# SCH_3S_10A_BMS_2022-07-15.net
KiCad netlist of a schematic drawn in EasyEDA
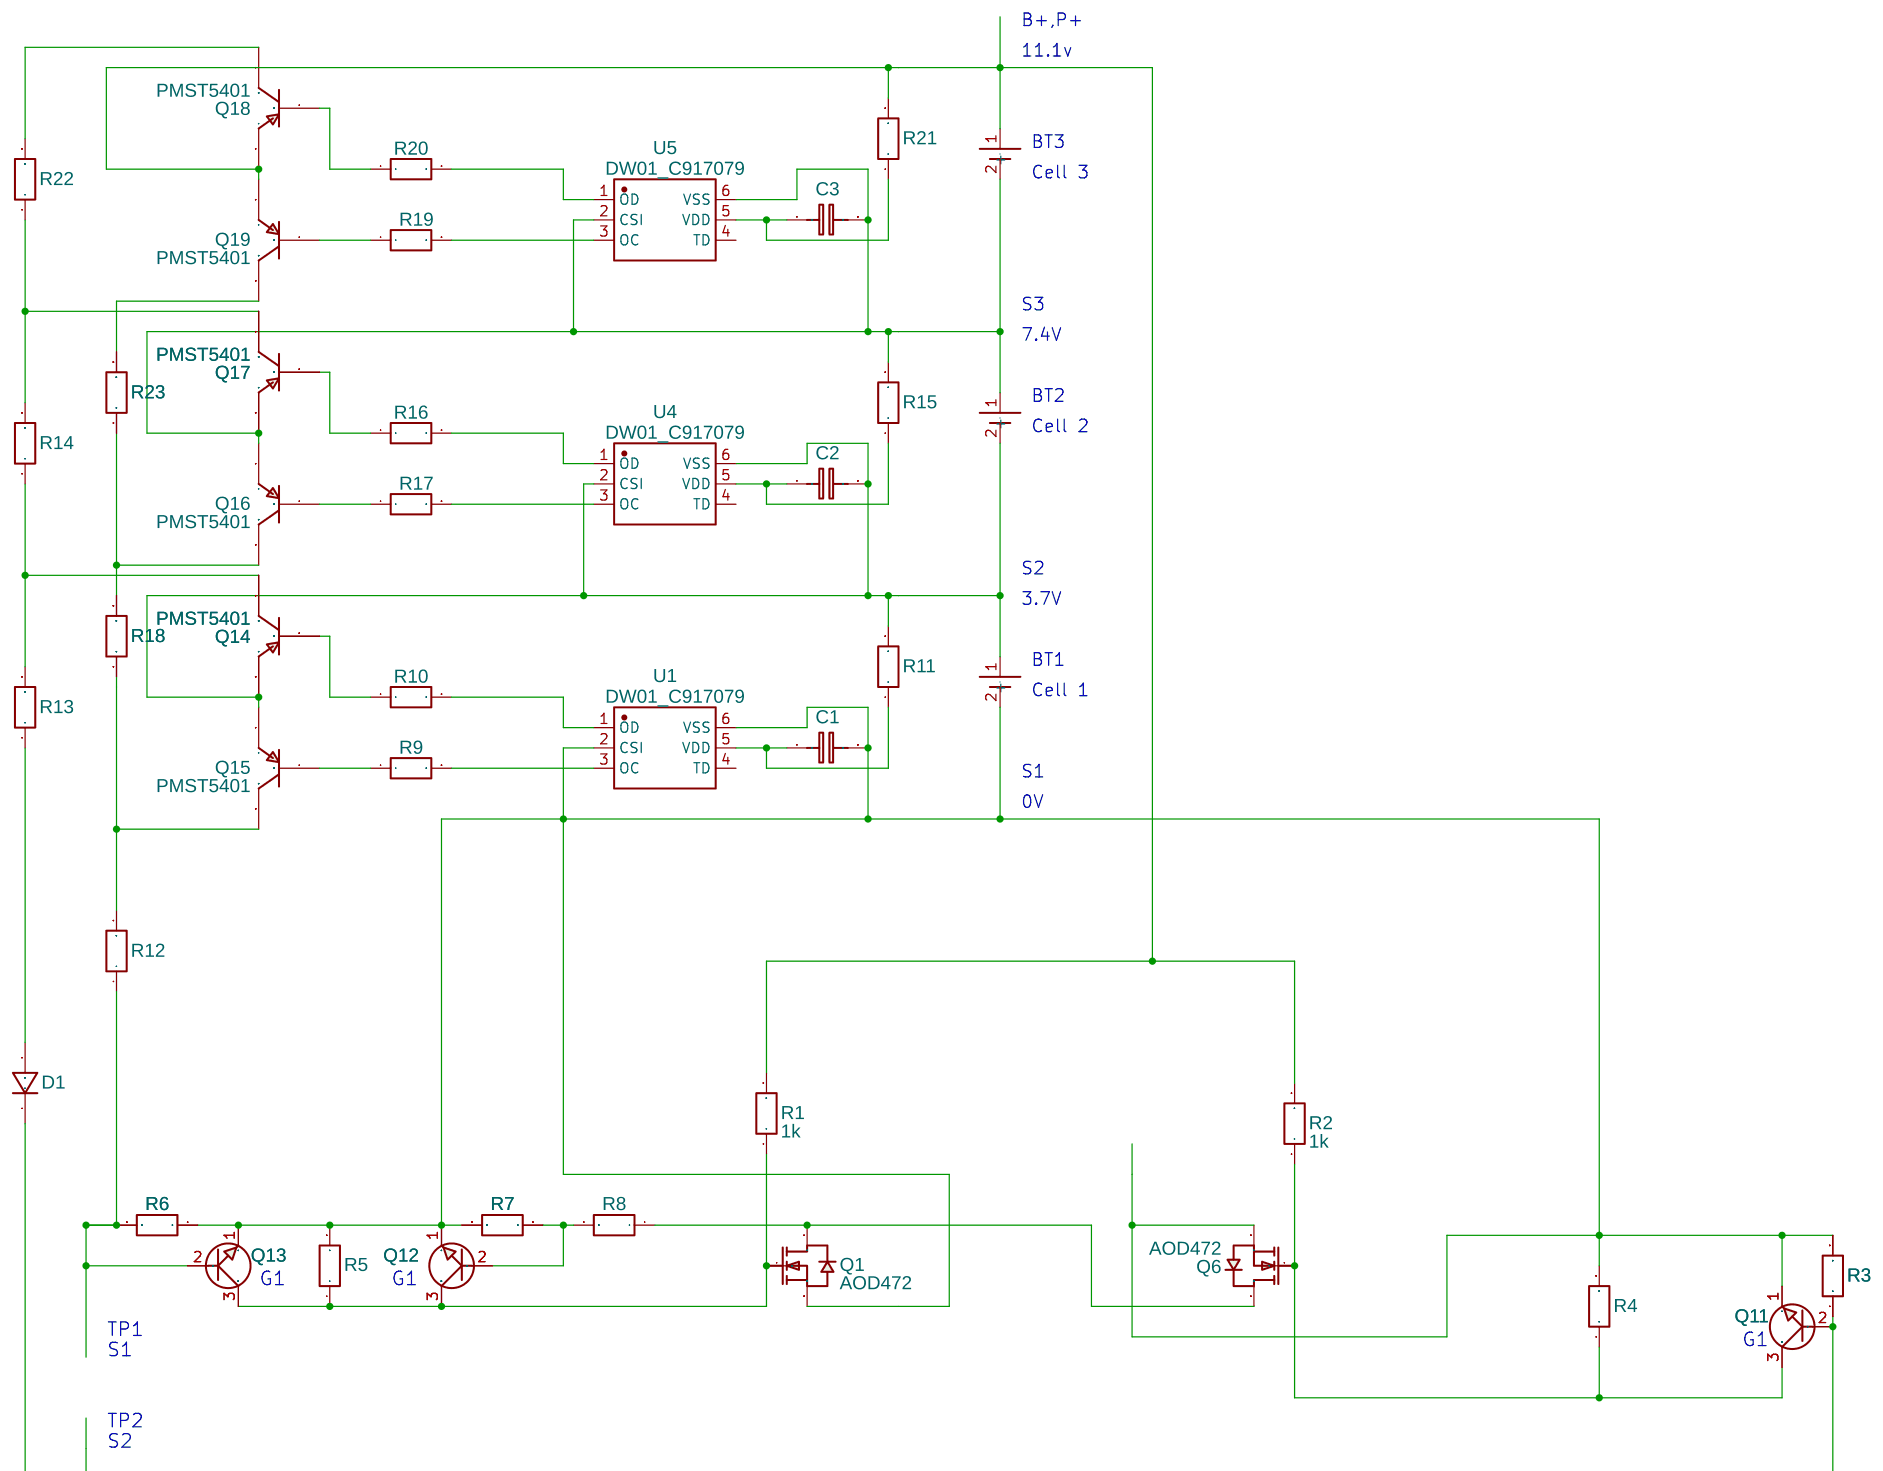
[diagram p0: 3s 10A Schematic]
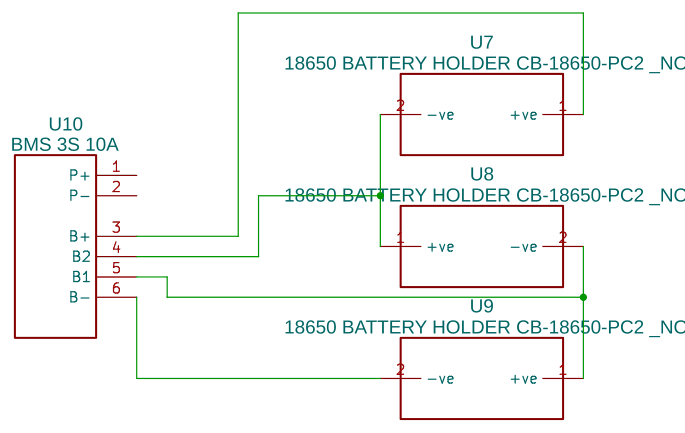
[diagram p1: 12v connection]

(export (version "E")
  (design (tool "Eeschema 10.0.6"))
  (components
    (comp (ref "C1") (value "0.1u") (libsource (lib "") (part "C_0603_EU")))
    (comp (ref "C2") (value "0.1u") (libsource (lib "") (part "C_0603_EU")))
    (comp (ref "C3") (value "0.1u") (libsource (lib "") (part "C_0603_EU")))
    (comp (ref "D1")
      (value "1N4007W")
      (fields (field (name "BOM_Supplier Part") "C328592"))
      (libsource (lib "") (part "1N4007W"))
    )
    (comp (ref "Q1")
      (value "AOD472")
      (fields (field (name "BOM_Supplier Part") "C693172"))
      (libsource (lib "") (part "AOD472"))
    )
    (comp (ref "Q6")
      (value "AOD472")
      (fields (field (name "BOM_Supplier Part") "C693172"))
      (libsource (lib "") (part "AOD472_1"))
    )
    (comp (ref "Q11") (value "2N2222") (libsource (lib "") (part "2N2222")))
    (comp (ref "Q12") (value "2N2222") (libsource (lib "") (part "2N2222")))
    (comp (ref "Q13") (value "2N2222") (libsource (lib "") (part "2N2222_1")))
    (comp (ref "Q14") (value "PMST5401") (libsource (lib "") (part "PMST5401_1")))
    (comp (ref "Q15") (value "PMST5401") (libsource (lib "") (part "PMST5401")))
    (comp (ref "Q16") (value "PMST5401") (libsource (lib "") (part "PMST5401")))
    (comp (ref "Q17") (value "PMST5401") (libsource (lib "") (part "PMST5401_1")))
    (comp (ref "Q18") (value "PMST5401") (libsource (lib "") (part "PMST5401_1")))
    (comp (ref "Q19") (value "PMST5401") (libsource (lib "") (part "PMST5401")))
    (comp (ref "R1") (value "1k") (libsource (lib "") (part "R_0603_EU_1")))
    (comp (ref "R2") (value "1k") (libsource (lib "") (part "R_0603_EU_1")))
    (comp (ref "R3") (value "1k") (libsource (lib "") (part "R_0603_EU_1")))
    (comp (ref "R4") (value "1k") (libsource (lib "") (part "R_0603_EU_1")))
    (comp (ref "R5") (value "1k") (libsource (lib "") (part "R_0603_EU_1")))
    (comp (ref "R6") (value "1k") (libsource (lib "") (part "R_0603_EU")))
    (comp (ref "R7") (value "1k") (libsource (lib "") (part "R_0603_EU")))
    (comp (ref "R8") (value "1k") (libsource (lib "") (part "R_0603_EU")))
    (comp (ref "R9") (value "1k") (libsource (lib "") (part "R_0603_EU_2")))
    (comp (ref "R10") (value "1k") (libsource (lib "") (part "R_0603_EU_2")))
    (comp (ref "R11") (value "1k") (libsource (lib "") (part "R_0603_EU_1")))
    (comp (ref "R12") (value "1k") (libsource (lib "") (part "R_0603_EU_1")))
    (comp (ref "R13") (value "1k") (libsource (lib "") (part "R_0603_EU_1")))
    (comp (ref "R14") (value "1k") (libsource (lib "") (part "R_0603_EU_1")))
    (comp (ref "R15") (value "1k") (libsource (lib "") (part "R_0603_EU_1")))
    (comp (ref "R16") (value "1k") (libsource (lib "") (part "R_0603_EU_2")))
    (comp (ref "R17") (value "1k") (libsource (lib "") (part "R_0603_EU_2")))
    (comp (ref "R18") (value "1k") (libsource (lib "") (part "R_0603_EU_1")))
    (comp (ref "R19") (value "1k") (libsource (lib "") (part "R_0603_EU_2")))
    (comp (ref "R20") (value "1k") (libsource (lib "") (part "R_0603_EU_2")))
    (comp (ref "R21") (value "1k") (libsource (lib "") (part "R_0603_EU_1")))
    (comp (ref "R22") (value "1k") (libsource (lib "") (part "R_0603_EU_1")))
    (comp (ref "R23") (value "1k") (libsource (lib "") (part "R_0603_EU_1")))
    (comp (ref "U1")
      (value "DW01_C917079")
      (fields (field (name "BOM_Manufacturer Part") "DW01") (field (name "BOM_Supplier Part") "C917079"))
      (libsource (lib "") (part "DW01_C917079"))
    )
    (comp (ref "U2") (value "Li-ion battery") (libsource (lib "") (part "Li-ion battery")))
    (comp (ref "U3") (value "Li-ion battery") (libsource (lib "") (part "Li-ion battery")))
    (comp (ref "U4")
      (value "DW01_C917079")
      (fields (field (name "BOM_Manufacturer Part") "DW01") (field (name "BOM_Supplier Part") "C917079"))
      (libsource (lib "") (part "DW01_C917079"))
    )
    (comp (ref "U5")
      (value "DW01_C917079")
      (fields (field (name "BOM_Manufacturer Part") "DW01") (field (name "BOM_Supplier Part") "C917079"))
      (libsource (lib "") (part "DW01_C917079"))
    )
    (comp (ref "U6") (value "Li-ion battery") (libsource (lib "") (part "Li-ion battery")))
    (comp (ref "U7")
      (value "18650 BATTERY HOLDER CB-18650-PC2 _NOTEMP COPY")
      (libsource (lib "") (part "18650 BATTERY HOLDER CB-18650-PC2 _NOTEMP COPY_1"))
    )
    (comp (ref "U8")
      (value "18650 BATTERY HOLDER CB-18650-PC2 _NOTEMP COPY")
      (libsource (lib "") (part "18650 BATTERY HOLDER CB-18650-PC2 _NOTEMP COPY"))
    )
    (comp (ref "U9")
      (value "18650 BATTERY HOLDER CB-18650-PC2 _NOTEMP COPY")
      (libsource (lib "") (part "18650 BATTERY HOLDER CB-18650-PC2 _NOTEMP COPY_1"))
    )
    (comp (ref "U10") (value "BMS 3S 10A") (libsource (lib "") (part "BMS 3S 10A")))
  )
  (nets
    (net (code "1") (name "Net-(D1-Pad2)") (class "Default")
      (node (ref "D1") (pin "2") (pinfunction "2_2") (pintype "unspecified"))
      (node (ref "R13") (pin "1") (pinfunction "1_1") (pintype "unspecified"))
    )
    (net (code "2") (name "Net-(Q1-D)") (class "Default")
      (node (ref "Q1") (pin "2") (pinfunction "D_2") (pintype "unspecified"))
      (node (ref "Q6") (pin "2") (pinfunction "D_2") (pintype "unspecified"))
      (node (ref "R8") (pin "1") (pinfunction "1_1") (pintype "unspecified"))
    )
    (net (code "3") (name "Net-(Q1-G)") (class "Default")
      (node (ref "Q1") (pin "1") (pinfunction "G_1") (pintype "unspecified"))
      (node (ref "Q12") (pin "3") (pinfunction "C_3") (pintype "unspecified"))
      (node (ref "Q13") (pin "3") (pinfunction "C_3") (pintype "unspecified"))
      (node (ref "R1") (pin "1") (pinfunction "1_1") (pintype "unspecified"))
      (node (ref "R5") (pin "1") (pinfunction "1_1") (pintype "unspecified"))
    )
    (net (code "4") (name "Net-(Q1-S)") (class "Default")
      (node (ref "C1") (pin "2") (pinfunction "2_2") (pintype "unspecified"))
      (node (ref "Q1") (pin "3") (pinfunction "S_3") (pintype "unspecified"))
      (node (ref "Q11") (pin "1") (pinfunction "E_1") (pintype "unspecified"))
      (node (ref "Q12") (pin "1") (pinfunction "E_1") (pintype "unspecified"))
      (node (ref "Q13") (pin "1") (pinfunction "E_1") (pintype "unspecified"))
      (node (ref "Q6") (pin "3") (pinfunction "S_3") (pintype "unspecified"))
      (node (ref "R3") (pin "2") (pinfunction "2_2") (pintype "unspecified"))
      (node (ref "R4") (pin "2") (pinfunction "2_2") (pintype "unspecified"))
      (node (ref "R5") (pin "2") (pinfunction "2_2") (pintype "unspecified"))
      (node (ref "R6") (pin "1") (pinfunction "1_1") (pintype "unspecified"))
      (node (ref "R7") (pin "2") (pinfunction "2_2") (pintype "unspecified"))
      (node (ref "U1") (pin "2") (pinfunction "CSI_2") (pintype "unspecified"))
      (node (ref "U1") (pin "6") (pinfunction "VSS_6") (pintype "unspecified"))
      (node (ref "U2") (pin "2") (pinfunction "-_2") (pintype "unspecified"))
    )
    (net (code "5") (name "Net-(Q11-B)") (class "Default")
      (node (ref "D1") (pin "1") (pinfunction "1_1") (pintype "unspecified"))
      (node (ref "Q11") (pin "2") (pinfunction "B_2") (pintype "input"))
      (node (ref "R3") (pin "1") (pinfunction "1_1") (pintype "unspecified"))
    )
    (net (code "6") (name "Net-(Q11-C)") (class "Default")
      (node (ref "Q11") (pin "3") (pinfunction "C_3") (pintype "unspecified"))
      (node (ref "Q6") (pin "1") (pinfunction "G_1") (pintype "unspecified"))
      (node (ref "R2") (pin "1") (pinfunction "1_1") (pintype "unspecified"))
      (node (ref "R4") (pin "1") (pinfunction "1_1") (pintype "unspecified"))
    )
    (net (code "7") (name "Net-(Q12-B)") (class "Default")
      (node (ref "Q12") (pin "2") (pinfunction "B_2") (pintype "input"))
      (node (ref "R7") (pin "1") (pinfunction "1_1") (pintype "unspecified"))
      (node (ref "R8") (pin "2") (pinfunction "2_2") (pintype "unspecified"))
    )
    (net (code "8") (name "Net-(Q13-B)") (class "Default")
      (node (ref "Q13") (pin "2") (pinfunction "B_2") (pintype "input"))
      (node (ref "R12") (pin "1") (pinfunction "1_1") (pintype "unspecified"))
      (node (ref "R6") (pin "2") (pinfunction "2_2") (pintype "unspecified"))
    )
    (net (code "9") (name "Net-(Q14-B)") (class "Default")
      (node (ref "Q14") (pin "1") (pinfunction "B_1") (pintype "unspecified"))
      (node (ref "R10") (pin "1") (pinfunction "1_1") (pintype "unspecified"))
    )
    (net (code "10") (name "Net-(Q14-C)") (class "Default")
      (node (ref "Q14") (pin "3") (pinfunction "C_3") (pintype "unspecified"))
      (node (ref "R13") (pin "2") (pinfunction "2_2") (pintype "unspecified"))
      (node (ref "R14") (pin "1") (pinfunction "1_1") (pintype "unspecified"))
    )
    (net (code "11") (name "Net-(Q14-E)") (class "Default")
      (node (ref "C2") (pin "2") (pinfunction "2_2") (pintype "unspecified"))
      (node (ref "Q14") (pin "2") (pinfunction "E_2") (pintype "unspecified"))
      (node (ref "Q15") (pin "2") (pinfunction "E_2") (pintype "unspecified"))
      (node (ref "R11") (pin "2") (pinfunction "2_2") (pintype "unspecified"))
      (node (ref "U2") (pin "1") (pinfunction "+_1") (pintype "unspecified"))
      (node (ref "U3") (pin "2") (pinfunction "-_2") (pintype "unspecified"))
      (node (ref "U4") (pin "2") (pinfunction "CSI_2") (pintype "unspecified"))
      (node (ref "U4") (pin "6") (pinfunction "VSS_6") (pintype "unspecified"))
    )
    (net (code "12") (name "Net-(Q15-B)") (class "Default")
      (node (ref "Q15") (pin "1") (pinfunction "B_1") (pintype "unspecified"))
      (node (ref "R9") (pin "1") (pinfunction "1_1") (pintype "unspecified"))
    )
    (net (code "13") (name "Net-(Q15-C)") (class "Default")
      (node (ref "Q15") (pin "3") (pinfunction "C_3") (pintype "unspecified"))
      (node (ref "R12") (pin "2") (pinfunction "2_2") (pintype "unspecified"))
      (node (ref "R18") (pin "1") (pinfunction "1_1") (pintype "unspecified"))
    )
    (net (code "14") (name "Net-(Q16-B)") (class "Default")
      (node (ref "Q16") (pin "1") (pinfunction "B_1") (pintype "unspecified"))
      (node (ref "R17") (pin "1") (pinfunction "1_1") (pintype "unspecified"))
    )
    (net (code "15") (name "Net-(Q16-C)") (class "Default")
      (node (ref "Q16") (pin "3") (pinfunction "C_3") (pintype "unspecified"))
      (node (ref "R18") (pin "2") (pinfunction "2_2") (pintype "unspecified"))
      (node (ref "R23") (pin "1") (pinfunction "1_1") (pintype "unspecified"))
    )
    (net (code "16") (name "Net-(Q16-E)") (class "Default")
      (node (ref "C3") (pin "2") (pinfunction "2_2") (pintype "unspecified"))
      (node (ref "Q16") (pin "2") (pinfunction "E_2") (pintype "unspecified"))
      (node (ref "Q17") (pin "2") (pinfunction "E_2") (pintype "unspecified"))
      (node (ref "R15") (pin "2") (pinfunction "2_2") (pintype "unspecified"))
      (node (ref "U3") (pin "1") (pinfunction "+_1") (pintype "unspecified"))
      (node (ref "U5") (pin "2") (pinfunction "CSI_2") (pintype "unspecified"))
      (node (ref "U5") (pin "6") (pinfunction "VSS_6") (pintype "unspecified"))
      (node (ref "U6") (pin "2") (pinfunction "-_2") (pintype "unspecified"))
    )
    (net (code "17") (name "Net-(Q17-B)") (class "Default")
      (node (ref "Q17") (pin "1") (pinfunction "B_1") (pintype "unspecified"))
      (node (ref "R16") (pin "1") (pinfunction "1_1") (pintype "unspecified"))
    )
    (net (code "18") (name "Net-(Q17-C)") (class "Default")
      (node (ref "Q17") (pin "3") (pinfunction "C_3") (pintype "unspecified"))
      (node (ref "R14") (pin "2") (pinfunction "2_2") (pintype "unspecified"))
      (node (ref "R22") (pin "1") (pinfunction "1_1") (pintype "unspecified"))
    )
    (net (code "19") (name "Net-(Q18-B)") (class "Default")
      (node (ref "Q18") (pin "1") (pinfunction "B_1") (pintype "unspecified"))
      (node (ref "R20") (pin "1") (pinfunction "1_1") (pintype "unspecified"))
    )
    (net (code "20") (name "Net-(Q18-C)") (class "Default")
      (node (ref "Q18") (pin "3") (pinfunction "C_3") (pintype "unspecified"))
      (node (ref "R22") (pin "2") (pinfunction "2_2") (pintype "unspecified"))
    )
    (net (code "21") (name "Net-(Q18-E)") (class "Default")
      (node (ref "Q18") (pin "2") (pinfunction "E_2") (pintype "unspecified"))
      (node (ref "Q19") (pin "2") (pinfunction "E_2") (pintype "unspecified"))
      (node (ref "R1") (pin "2") (pinfunction "2_2") (pintype "unspecified"))
      (node (ref "R2") (pin "2") (pinfunction "2_2") (pintype "unspecified"))
      (node (ref "R21") (pin "2") (pinfunction "2_2") (pintype "unspecified"))
      (node (ref "U6") (pin "1") (pinfunction "+_1") (pintype "unspecified"))
    )
    (net (code "22") (name "Net-(Q19-B)") (class "Default")
      (node (ref "Q19") (pin "1") (pinfunction "B_1") (pintype "unspecified"))
      (node (ref "R19") (pin "1") (pinfunction "1_1") (pintype "unspecified"))
    )
    (net (code "23") (name "Net-(Q19-C)") (class "Default")
      (node (ref "Q19") (pin "3") (pinfunction "C_3") (pintype "unspecified"))
      (node (ref "R23") (pin "2") (pinfunction "2_2") (pintype "unspecified"))
    )
    (net (code "24") (name "Net-(U1-OC)") (class "Default")
      (node (ref "R9") (pin "2") (pinfunction "2_2") (pintype "unspecified"))
      (node (ref "U1") (pin "3") (pinfunction "OC_3") (pintype "unspecified"))
    )
    (net (code "25") (name "Net-(U1-OD)") (class "Default")
      (node (ref "R10") (pin "2") (pinfunction "2_2") (pintype "unspecified"))
      (node (ref "U1") (pin "1") (pinfunction "OD_1") (pintype "unspecified"))
    )
    (net (code "26") (name "Net-(U1-VDD)") (class "Default")
      (node (ref "C1") (pin "1") (pinfunction "1_1") (pintype "unspecified"))
      (node (ref "R11") (pin "1") (pinfunction "1_1") (pintype "unspecified"))
      (node (ref "U1") (pin "5") (pinfunction "VDD_5") (pintype "unspecified"))
    )
    (net (code "27") (name "Net-(U4-OC)") (class "Default")
      (node (ref "R17") (pin "2") (pinfunction "2_2") (pintype "unspecified"))
      (node (ref "U4") (pin "3") (pinfunction "OC_3") (pintype "unspecified"))
    )
    (net (code "28") (name "Net-(U4-OD)") (class "Default")
      (node (ref "R16") (pin "2") (pinfunction "2_2") (pintype "unspecified"))
      (node (ref "U4") (pin "1") (pinfunction "OD_1") (pintype "unspecified"))
    )
    (net (code "29") (name "Net-(U4-VDD)") (class "Default")
      (node (ref "C2") (pin "1") (pinfunction "1_1") (pintype "unspecified"))
      (node (ref "R15") (pin "1") (pinfunction "1_1") (pintype "unspecified"))
      (node (ref "U4") (pin "5") (pinfunction "VDD_5") (pintype "unspecified"))
    )
    (net (code "30") (name "Net-(U5-OC)") (class "Default")
      (node (ref "R19") (pin "2") (pinfunction "2_2") (pintype "unspecified"))
      (node (ref "U5") (pin "3") (pinfunction "OC_3") (pintype "unspecified"))
    )
    (net (code "31") (name "Net-(U5-OD)") (class "Default")
      (node (ref "R20") (pin "2") (pinfunction "2_2") (pintype "unspecified"))
      (node (ref "U5") (pin "1") (pinfunction "OD_1") (pintype "unspecified"))
    )
    (net (code "32") (name "Net-(U5-VDD)") (class "Default")
      (node (ref "C3") (pin "1") (pinfunction "1_1") (pintype "unspecified"))
      (node (ref "R21") (pin "1") (pinfunction "1_1") (pintype "unspecified"))
      (node (ref "U5") (pin "5") (pinfunction "VDD_5") (pintype "unspecified"))
    )
    (net (code "33") (name "Net-(U10-B+)") (class "Default")
      (node (ref "U10") (pin "3") (pinfunction "B+_3") (pintype "unspecified"))
      (node (ref "U7") (pin "1") (pinfunction "+ve_1") (pintype "passive"))
    )
    (net (code "34") (name "Net-(U10-B-)") (class "Default")
      (node (ref "U10") (pin "6") (pinfunction "B-_6") (pintype "unspecified"))
      (node (ref "U9") (pin "2") (pinfunction "-ve_2") (pintype "passive"))
    )
    (net (code "35") (name "Net-(U10-B1)") (class "Default")
      (node (ref "U10") (pin "5") (pinfunction "B1_5") (pintype "unspecified"))
      (node (ref "U8") (pin "2") (pinfunction "-ve_2") (pintype "passive"))
      (node (ref "U9") (pin "1") (pinfunction "+ve_1") (pintype "passive"))
    )
    (net (code "36") (name "Net-(U10-B2)") (class "Default")
      (node (ref "U10") (pin "4") (pinfunction "B2_4") (pintype "unspecified"))
      (node (ref "U7") (pin "2") (pinfunction "-ve_2") (pintype "passive"))
      (node (ref "U8") (pin "1") (pinfunction "+ve_1") (pintype "passive"))
    )
    (net (code "37") (name "unconnected-(U1-TD-Pad4)") (class "Default")
      (node (ref "U1") (pin "4") (pinfunction "TD_4") (pintype "unspecified"))
    )
    (net (code "38") (name "unconnected-(U4-TD-Pad4)") (class "Default")
      (node (ref "U4") (pin "4") (pinfunction "TD_4") (pintype "unspecified"))
    )
    (net (code "39") (name "unconnected-(U5-TD-Pad4)") (class "Default")
      (node (ref "U5") (pin "4") (pinfunction "TD_4") (pintype "unspecified"))
    )
    (net (code "40") (name "unconnected-(U10-P+-Pad1)") (class "Default")
      (node (ref "U10") (pin "1") (pinfunction "P+_1") (pintype "unspecified"))
    )
    (net (code "41") (name "unconnected-(U10-P--Pad2)") (class "Default")
      (node (ref "U10") (pin "2") (pinfunction "P-_2") (pintype "unspecified"))
    )
  )
)
